# EE209_Schematic.net
KiCad netlist of a schematic drawn in Altium Designer
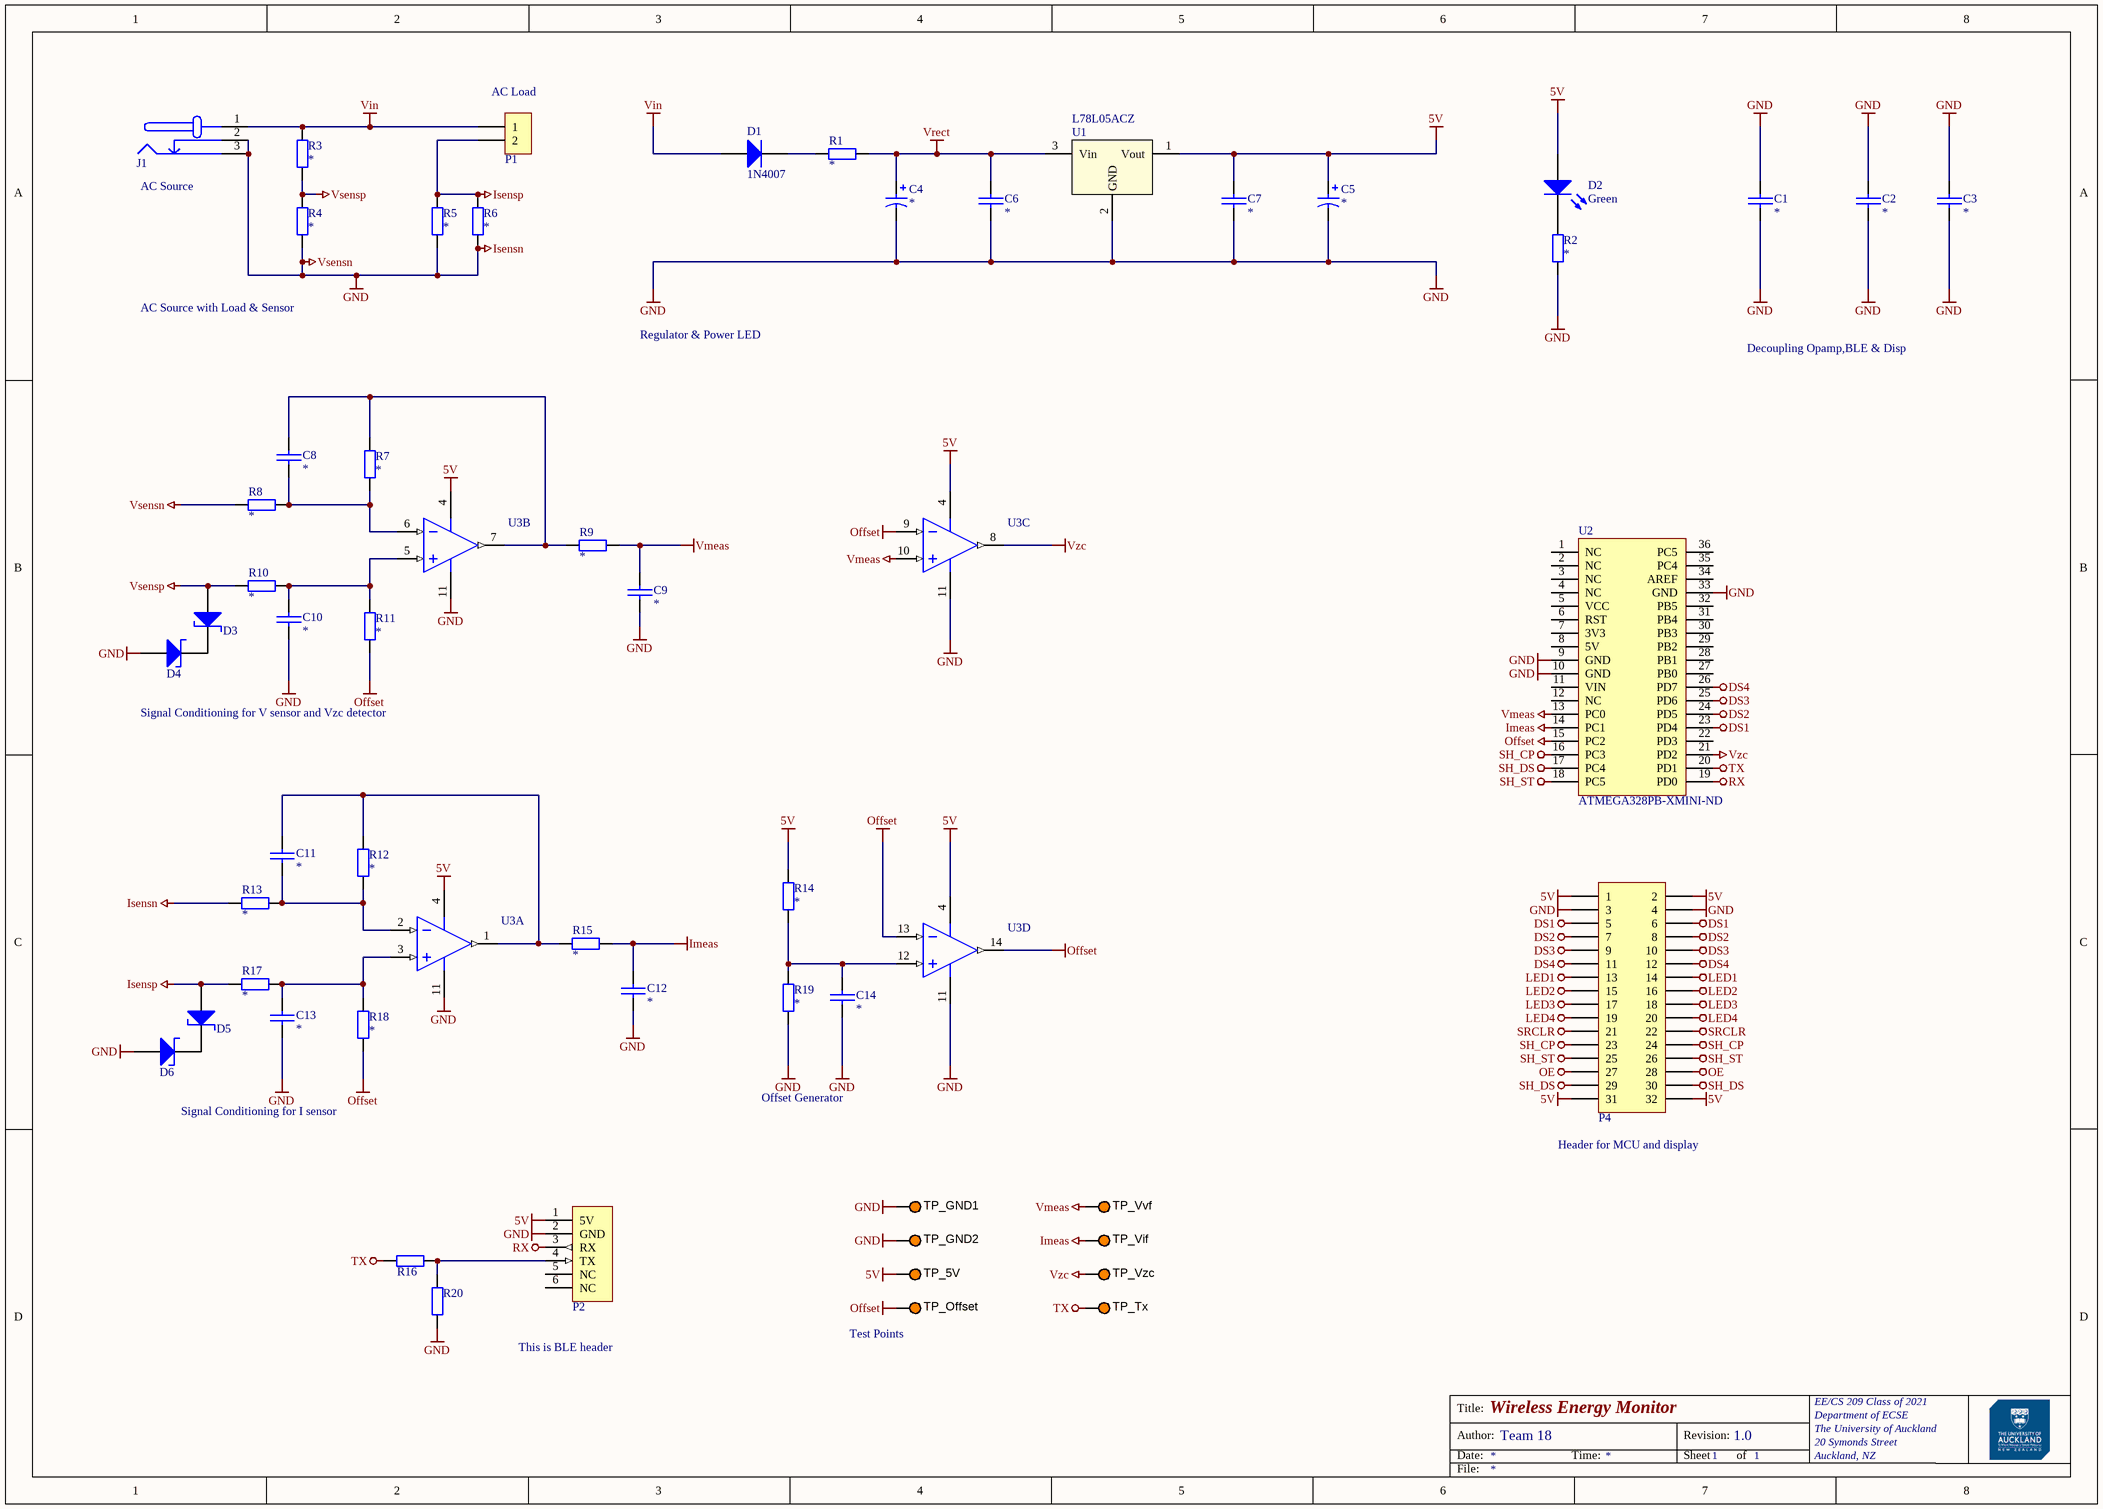
[diagram p0: EE209_Schematic.SchDoc]

(export (version "E")
  (design (tool "Eeschema 10.0.6"))
  (components
    (comp (ref "C1")
      (value "*")
      (footprint "CCAP-5P0")
      (description "TH ceramic capacitor with 5mm pitch")
      (libsource (lib "EE209_Library") (part "CerCap_TH_5P0"))
    )
    (comp (ref "C2")
      (value "*")
      (footprint "CCAP-5P0")
      (description "TH ceramic capacitor with 5mm pitch")
      (libsource (lib "EE209_Library") (part "CerCap_TH_5P0"))
    )
    (comp (ref "C3")
      (value "*")
      (footprint "CCAP-5P0")
      (description "TH ceramic capacitor with 5mm pitch")
      (libsource (lib "EE209_Library") (part "CerCap_TH_5P0"))
    )
    (comp (ref "C4")
      (value "*")
      (footprint "CAP-RAD-2.5mm Pitch")
      (description "Electrolytic capacitor with radial package, 2mm pitch and 5.2mm diameter")
      (fields (field (name "PUBLISHER") "Altium Limited"))
      (libsource (lib "EE209_Library") (part "ElecCap_TH_2P0"))
    )
    (comp (ref "C5")
      (value "*")
      (footprint "CAP-RAD-2.5mm Pitch")
      (description "Electrolytic capacitor with radial package, 2mm pitch and 5.2mm diameter")
      (fields (field (name "PUBLISHER") "Altium Limited"))
      (libsource (lib "EE209_Library") (part "ElecCap_TH_2P0"))
    )
    (comp (ref "C6")
      (value "*")
      (footprint "CCAP-5P0")
      (description "TH ceramic capacitor with 5mm pitch")
      (libsource (lib "EE209_Library") (part "CerCap_TH_5P0"))
    )
    (comp (ref "C7")
      (value "*")
      (footprint "CCAP-5P0")
      (description "TH ceramic capacitor with 5mm pitch")
      (libsource (lib "EE209_Library") (part "CerCap_TH_5P0"))
    )
    (comp (ref "C8")
      (value "*")
      (footprint "CCAP-5P0")
      (description "TH ceramic capacitor with 5mm pitch")
      (libsource (lib "EE209_Library") (part "CerCap_TH_5P0"))
    )
    (comp (ref "C9")
      (value "*")
      (footprint "CCAP-5P0")
      (description "TH ceramic capacitor with 5mm pitch")
      (libsource (lib "EE209_Library") (part "CerCap_TH_5P0"))
    )
    (comp (ref "C10")
      (value "*")
      (footprint "CCAP-5P0")
      (description "TH ceramic capacitor with 5mm pitch")
      (libsource (lib "EE209_Library") (part "CerCap_TH_5P0"))
    )
    (comp (ref "C11")
      (value "*")
      (footprint "CCAP-5P0")
      (description "TH ceramic capacitor with 5mm pitch")
      (libsource (lib "EE209_Library") (part "CerCap_TH_5P0"))
    )
    (comp (ref "C12")
      (value "*")
      (footprint "CCAP-5P0")
      (description "TH ceramic capacitor with 5mm pitch")
      (libsource (lib "EE209_Library") (part "CerCap_TH_5P0"))
    )
    (comp (ref "C13")
      (value "*")
      (footprint "CCAP-5P0")
      (description "TH ceramic capacitor with 5mm pitch")
      (libsource (lib "EE209_Library") (part "CerCap_TH_5P0"))
    )
    (comp (ref "C14")
      (value "*")
      (footprint "CCAP-5P0")
      (description "TH ceramic capacitor with 5mm pitch")
      (libsource (lib "EE209_Library") (part "CerCap_TH_5P0"))
    )
    (comp (ref "D1")
      (value "1N4007")
      (footprint "1N4007-MFG")
      (description "1N4007 1000V standard axial diode")
      (libsource (lib "EE209_Library") (part "1N4007_TH_4AX0"))
    )
    (comp (ref "D2")
      (value "Green")
      (footprint "LED")
      (description "Typical throughole GaAs LED with 2.54mm pitch")
      (fields (field (name "MANUFACTURER") "Generic Components") (field (name "PUBLISHER") "Altium Limited"))
      (libsource (lib "EE209_Library") (part "LED_TH_2P54"))
    )
    (comp (ref "D3")
      (value "BZX79-CXVX")
      (footprint "AXIAL-Zener-0.4")
      (description "Axial zener diode BZX79 series")
      (fields
        (field (name "MANUFACTURER") "Nexperia USA Inc.")
        (field (name "MANUFACTURER PART NUMBER") "BZX79-C4V7,143")
      )
      (libsource (lib "EE209_Library") (part "Zener_TH_4AX0"))
    )
    (comp (ref "D4")
      (value "BZX79-CXVX")
      (footprint "AXIAL-Zener-0.4")
      (description "Axial zener diode BZX79 series")
      (fields
        (field (name "MANUFACTURER") "Nexperia USA Inc.")
        (field (name "MANUFACTURER PART NUMBER") "BZX79-C4V7,143")
      )
      (libsource (lib "EE209_Library") (part "Zener_TH_4AX0"))
    )
    (comp (ref "D5")
      (value "BZX79-CXVX")
      (footprint "AXIAL-Zener-0.4")
      (description "Axial zener diode BZX79 series")
      (fields
        (field (name "MANUFACTURER") "Nexperia USA Inc.")
        (field (name "MANUFACTURER PART NUMBER") "BZX79-C4V7,143")
      )
      (libsource (lib "EE209_Library") (part "Zener_TH_4AX0"))
    )
    (comp (ref "D6")
      (value "BZX79-CXVX")
      (footprint "AXIAL-Zener-0.4")
      (description "Axial zener diode BZX79 series")
      (fields
        (field (name "MANUFACTURER") "Nexperia USA Inc.")
        (field (name "MANUFACTURER PART NUMBER") "BZX79-C4V7,143")
      )
      (libsource (lib "EE209_Library") (part "Zener_TH_4AX0"))
    )
    (comp (ref "J1")
      (value "DC barrel jack")
      (footprint "AC-Socket")
      (description "DC barrel jack connection to AC source")
      (libsource (lib "EE209_Library") (part "AC_Input"))
    )
    (comp (ref "P1")
      (value "Dual Banana Plugs")
      (footprint "Dual Banana Plug")
      (description "Dual banana plugs connection to the AC load")
      (fields (field (name "PUBLISHER") "Altium Limited"))
      (libsource (lib "EE209_Library") (part "AC_Output"))
    )
    (comp (ref "P2")
      (value "BLE Module Header")
      (footprint "HM10_HDR1X6")
      (description "2.54mm pitch 6-pin header for BLE module")
      (fields (field (name "PUBLISHER") "Altium Limited"))
      (libsource (lib "EE209_Library") (part "BLEModule_TH"))
    )
    (comp (ref "P4")
      (value "Display")
      (footprint "Display")
      (description "16-Pin Header Connecting Display")
      (libsource (lib "EE209_Library") (part "Display"))
    )
    (comp (ref "R1")
      (value "*")
      (footprint "AXIAL-0.4")
      (description "Through hole resistor")
      (fields (field (name "PUBLISHER") "Altium Limited"))
      (libsource (lib "EE209_Library") (part "Res_TH_0AX4"))
    )
    (comp (ref "R2")
      (value "*")
      (footprint "AXIAL-0.4")
      (description "Through hole resistor")
      (fields (field (name "PUBLISHER") "Altium Limited"))
      (libsource (lib "") (part "Res_TH_0AX4_1"))
    )
    (comp (ref "R3")
      (value "*")
      (footprint "AXIAL-0.4")
      (description "Through hole resistor")
      (fields (field (name "PUBLISHER") "Altium Limited"))
      (libsource (lib "") (part "Res_TH_0AX4_1"))
    )
    (comp (ref "R4")
      (value "*")
      (footprint "AXIAL-0.4")
      (description "Through hole resistor")
      (fields (field (name "PUBLISHER") "Altium Limited"))
      (libsource (lib "") (part "Res_TH_0AX4_1"))
    )
    (comp (ref "R5")
      (value "*")
      (footprint "AXIAL-0.4")
      (description "Through hole resistor")
      (fields (field (name "PUBLISHER") "Altium Limited"))
      (libsource (lib "") (part "Res_TH_0AX4_1"))
    )
    (comp (ref "R6")
      (value "*")
      (footprint "AXIAL-0.4")
      (description "Through hole resistor")
      (fields (field (name "PUBLISHER") "Altium Limited"))
      (libsource (lib "") (part "Res_TH_0AX4_1"))
    )
    (comp (ref "R7")
      (value "*")
      (footprint "AXIAL-0.4")
      (description "Through hole resistor")
      (fields (field (name "PUBLISHER") "Altium Limited"))
      (libsource (lib "") (part "Res_TH_0AX4_1"))
    )
    (comp (ref "R8")
      (value "*")
      (footprint "AXIAL-0.4")
      (description "Through hole resistor")
      (fields (field (name "PUBLISHER") "Altium Limited"))
      (libsource (lib "EE209_Library") (part "Res_TH_0AX4"))
    )
    (comp (ref "R9")
      (value "*")
      (footprint "AXIAL-0.4")
      (description "Through hole resistor")
      (fields (field (name "PUBLISHER") "Altium Limited"))
      (libsource (lib "EE209_Library") (part "Res_TH_0AX4"))
    )
    (comp (ref "R10")
      (value "*")
      (footprint "AXIAL-0.4")
      (description "Through hole resistor")
      (fields (field (name "PUBLISHER") "Altium Limited"))
      (libsource (lib "EE209_Library") (part "Res_TH_0AX4"))
    )
    (comp (ref "R11")
      (value "*")
      (footprint "AXIAL-0.4")
      (description "Through hole resistor")
      (fields (field (name "PUBLISHER") "Altium Limited"))
      (libsource (lib "") (part "Res_TH_0AX4_1"))
    )
    (comp (ref "R12")
      (value "*")
      (footprint "AXIAL-0.4")
      (description "Through hole resistor")
      (fields (field (name "PUBLISHER") "Altium Limited"))
      (libsource (lib "") (part "Res_TH_0AX4_1"))
    )
    (comp (ref "R13")
      (value "*")
      (footprint "AXIAL-0.4")
      (description "Through hole resistor")
      (fields (field (name "PUBLISHER") "Altium Limited"))
      (libsource (lib "EE209_Library") (part "Res_TH_0AX4"))
    )
    (comp (ref "R14")
      (value "*")
      (footprint "AXIAL-0.4")
      (description "Through hole resistor")
      (fields (field (name "PUBLISHER") "Altium Limited"))
      (libsource (lib "") (part "Res_TH_0AX4_1"))
    )
    (comp (ref "R15")
      (value "*")
      (footprint "AXIAL-0.4")
      (description "Through hole resistor")
      (fields (field (name "PUBLISHER") "Altium Limited"))
      (libsource (lib "EE209_Library") (part "Res_TH_0AX4"))
    )
    (comp (ref "R16")
      (value "*")
      (footprint "AXIAL-0.4")
      (description "Through hole resistor")
      (fields (field (name "PUBLISHER") "Altium Limited"))
      (libsource (lib "") (part "Res_TH_0AX4_2"))
    )
    (comp (ref "R17")
      (value "*")
      (footprint "AXIAL-0.4")
      (description "Through hole resistor")
      (fields (field (name "PUBLISHER") "Altium Limited"))
      (libsource (lib "EE209_Library") (part "Res_TH_0AX4"))
    )
    (comp (ref "R18")
      (value "*")
      (footprint "AXIAL-0.4")
      (description "Through hole resistor")
      (fields (field (name "PUBLISHER") "Altium Limited"))
      (libsource (lib "") (part "Res_TH_0AX4_1"))
    )
    (comp (ref "R19")
      (value "*")
      (footprint "AXIAL-0.4")
      (description "Through hole resistor")
      (fields (field (name "PUBLISHER") "Altium Limited"))
      (libsource (lib "") (part "Res_TH_0AX4_1"))
    )
    (comp (ref "R20")
      (value "*")
      (footprint "AXIAL-0.4")
      (description "Through hole resistor")
      (fields (field (name "PUBLISHER") "Altium Limited"))
      (libsource (lib "") (part "Res_TH_0AX4_1"))
    )
    (comp (ref "TP_5V")
      (value "5003")
      (footprint "TP_TH")
      (description "Test Point, Orange, 1-Pin THD, RoHS")
      (libsource (lib "EE209_Library") (part "TestPoint"))
    )
    (comp (ref "TP_GND1")
      (value "5003")
      (footprint "TP_TH")
      (description "Test Point, Orange, 1-Pin THD, RoHS")
      (libsource (lib "EE209_Library") (part "TestPoint"))
    )
    (comp (ref "TP_GND2")
      (value "5003")
      (footprint "TP_TH")
      (description "Test Point, Orange, 1-Pin THD, RoHS")
      (libsource (lib "EE209_Library") (part "TestPoint"))
    )
    (comp (ref "TP_Offset")
      (value "5003")
      (footprint "TP_TH")
      (description "Test Point, Orange, 1-Pin THD, RoHS")
      (libsource (lib "EE209_Library") (part "TestPoint"))
    )
    (comp (ref "TP_Tx")
      (value "5003")
      (footprint "TP_TH")
      (description "Test Point, Orange, 1-Pin THD, RoHS")
      (libsource (lib "EE209_Library") (part "TestPoint"))
    )
    (comp (ref "TP_Vif")
      (value "5003")
      (footprint "TP_TH")
      (description "Test Point, Orange, 1-Pin THD, RoHS")
      (libsource (lib "EE209_Library") (part "TestPoint"))
    )
    (comp (ref "TP_Vvf")
      (value "5003")
      (footprint "TP_TH")
      (description "Test Point, Orange, 1-Pin THD, RoHS")
      (libsource (lib "EE209_Library") (part "TestPoint"))
    )
    (comp (ref "TP_Vzc")
      (value "5003")
      (footprint "TP_TH")
      (description "Test Point, Orange, 1-Pin THD, RoHS")
      (libsource (lib "EE209_Library") (part "TestPoint"))
    )
    (comp (ref "U1")
      (value "L78L05ACZ")
      (footprint "TO-92")
      (description "Voltage Regulator 5V")
      (fields
        (field (name "MANUFACTURER") "ON Semiconductor")
        (field (name "MANUFACTURER PART NUMBER") "LM78L05ACZX")
      )
      (libsource (lib "EE209_Library") (part "L78L05_TH_TO92"))
    )
    (comp (ref "U2")
      (value "ATmega328PB Xplained Mini Header")
      (footprint "ATmeg328P Xplained")
      (description "Dual 18-pin headers connecting to ATmega328PB Xplained Mini")
      (fields
        (field (name "MANUFACTURER") "Microchip Technology")
        (field (name "MANUFACTURER PART NUMBER") "ATMEGA328PB-XMINI")
        (field (name "SUPPLIER PART NUMBER 1") "ATMEGA328PB-XMINI-ND")
      )
      (libsource (lib "EE209_Library") (part "ATmega328PBXplained_TH"))
    )
    (comp (ref "U3")
      (value "LM324")
      (footprint "DIP-14")
      (description "IC OPAMP GP 14DIP")
      (fields
        (field (name "MANUFACTURER") "ON Semiconductor")
        (field (name "MANUFACTURER PART NUMBER") "LM324N")
      )
      (libsource (lib "EE209_Library") (part "LM324N_TH_DIP16"))
    )
  )
  (nets
    (net (code "1") (name "5V") (class "Default")
      (node (ref "C5") (pin "1") (pinfunction "1_1") (pintype "passive"))
      (node (ref "C7") (pin "1") (pinfunction "1_1") (pintype "passive"))
      (node (ref "D2") (pin "1") (pinfunction "A_1") (pintype "passive"))
      (node (ref "P2") (pin "1") (pinfunction "5V_1") (pintype "passive"))
      (node (ref "P4") (pin "1") (pinfunction "1_1") (pintype "passive"))
      (node (ref "P4") (pin "2") (pinfunction "2_2") (pintype "passive"))
      (node (ref "P4") (pin "31") (pinfunction "31_31") (pintype "passive"))
      (node (ref "P4") (pin "32") (pinfunction "32_32") (pintype "passive"))
      (node (ref "R14") (pin "2") (pinfunction "2_2") (pintype "passive"))
      (node (ref "TP_5V") (pin "1") (pinfunction "1_1") (pintype "passive"))
      (node (ref "U1") (pin "1") (pinfunction "Vout_1") (pintype "passive"))
      (node (ref "U3") (pin "4") (pinfunction "VDD_4") (pintype "power_in"))
    )
    (net (code "2") (name "DS1") (class "Default")
      (node (ref "P4") (pin "5") (pinfunction "5_5") (pintype "passive"))
      (node (ref "P4") (pin "6") (pinfunction "6_6") (pintype "passive"))
      (node (ref "U2") (pin "23") (pinfunction "PD4_23") (pintype "passive"))
    )
    (net (code "3") (name "DS2") (class "Default")
      (node (ref "P4") (pin "7") (pinfunction "7_7") (pintype "passive"))
      (node (ref "P4") (pin "8") (pinfunction "8_8") (pintype "passive"))
      (node (ref "U2") (pin "24") (pinfunction "PD5_24") (pintype "passive"))
    )
    (net (code "4") (name "DS3") (class "Default")
      (node (ref "P4") (pin "10") (pinfunction "10_10") (pintype "passive"))
      (node (ref "P4") (pin "9") (pinfunction "9_9") (pintype "passive"))
      (node (ref "U2") (pin "25") (pinfunction "PD6_25") (pintype "passive"))
    )
    (net (code "5") (name "DS4") (class "Default")
      (node (ref "P4") (pin "11") (pinfunction "11_11") (pintype "passive"))
      (node (ref "P4") (pin "12") (pinfunction "12_12") (pintype "passive"))
      (node (ref "U2") (pin "26") (pinfunction "PD7_26") (pintype "passive"))
    )
    (net (code "6") (name "GND") (class "Default")
      (node (ref "C1") (pin "1") (pinfunction "1_1") (pintype "passive"))
      (node (ref "C1") (pin "2") (pinfunction "2_2") (pintype "passive"))
      (node (ref "C10") (pin "2") (pinfunction "2_2") (pintype "passive"))
      (node (ref "C12") (pin "2") (pinfunction "2_2") (pintype "passive"))
      (node (ref "C13") (pin "2") (pinfunction "2_2") (pintype "passive"))
      (node (ref "C14") (pin "2") (pinfunction "2_2") (pintype "passive"))
      (node (ref "C2") (pin "1") (pinfunction "1_1") (pintype "passive"))
      (node (ref "C2") (pin "2") (pinfunction "2_2") (pintype "passive"))
      (node (ref "C3") (pin "1") (pinfunction "1_1") (pintype "passive"))
      (node (ref "C3") (pin "2") (pinfunction "2_2") (pintype "passive"))
      (node (ref "C4") (pin "2") (pinfunction "2_2") (pintype "passive"))
      (node (ref "C5") (pin "2") (pinfunction "2_2") (pintype "passive"))
      (node (ref "C6") (pin "2") (pinfunction "2_2") (pintype "passive"))
      (node (ref "C7") (pin "2") (pinfunction "2_2") (pintype "passive"))
      (node (ref "C9") (pin "2") (pinfunction "2_2") (pintype "passive"))
      (node (ref "D4") (pin "1") (pinfunction "A_1") (pintype "passive"))
      (node (ref "D6") (pin "1") (pinfunction "A_1") (pintype "passive"))
      (node (ref "J1") (pin "2") (pinfunction "GND_ALT_2") (pintype "power_in"))
      (node (ref "J1") (pin "3") (pinfunction "GND_3") (pintype "power_in"))
      (node (ref "P2") (pin "2") (pinfunction "GND_2") (pintype "passive"))
      (node (ref "P4") (pin "3") (pinfunction "3_3") (pintype "passive"))
      (node (ref "P4") (pin "4") (pinfunction "4_4") (pintype "passive"))
      (node (ref "R13") (pin "1") (pinfunction "1_1") (pintype "passive"))
      (node (ref "R19") (pin "1") (pinfunction "1_1") (pintype "passive"))
      (node (ref "R2") (pin "1") (pinfunction "1_1") (pintype "passive"))
      (node (ref "R20") (pin "1") (pinfunction "1_1") (pintype "passive"))
      (node (ref "R4") (pin "1") (pinfunction "1_1") (pintype "passive"))
      (node (ref "R5") (pin "1") (pinfunction "1_1") (pintype "passive"))
      (node (ref "R6") (pin "1") (pinfunction "1_1") (pintype "passive"))
      (node (ref "R8") (pin "1") (pinfunction "1_1") (pintype "passive"))
      (node (ref "TP_GND1") (pin "1") (pinfunction "1_1") (pintype "passive"))
      (node (ref "TP_GND2") (pin "1") (pinfunction "1_1") (pintype "passive"))
      (node (ref "U1") (pin "2") (pinfunction "GND_2") (pintype "passive"))
      (node (ref "U2") (pin "10") (pinfunction "GND_10") (pintype "power_in"))
      (node (ref "U2") (pin "33") (pinfunction "GND_33") (pintype "passive"))
      (node (ref "U2") (pin "9") (pinfunction "GND_9") (pintype "power_in"))
      (node (ref "U3") (pin "11") (pinfunction "VSS_11") (pintype "power_in"))
    )
    (net (code "7") (name "Imeas") (class "Default")
      (node (ref "C12") (pin "1") (pinfunction "1_1") (pintype "passive"))
      (node (ref "R15") (pin "2") (pinfunction "2_2") (pintype "passive"))
      (node (ref "TP_Vif") (pin "1") (pinfunction "1_1") (pintype "passive"))
      (node (ref "U2") (pin "14") (pinfunction "PC1_14") (pintype "passive"))
    )
    (net (code "8") (name "Isensp") (class "Default")
      (node (ref "D5") (pin "1") (pinfunction "A_1") (pintype "passive"))
      (node (ref "P1") (pin "2") (pinfunction "2_2") (pintype "passive"))
      (node (ref "R17") (pin "1") (pinfunction "1_1") (pintype "passive"))
      (node (ref "R5") (pin "2") (pinfunction "2_2") (pintype "passive"))
      (node (ref "R6") (pin "2") (pinfunction "2_2") (pintype "passive"))
    )
    (net (code "9") (name "LED1") (class "Default")
      (node (ref "P4") (pin "13") (pinfunction "13_13") (pintype "passive"))
      (node (ref "P4") (pin "14") (pinfunction "14_14") (pintype "passive"))
    )
    (net (code "10") (name "LED2") (class "Default")
      (node (ref "P4") (pin "15") (pinfunction "15_15") (pintype "passive"))
      (node (ref "P4") (pin "16") (pinfunction "16_16") (pintype "passive"))
    )
    (net (code "11") (name "LED3") (class "Default")
      (node (ref "P4") (pin "17") (pinfunction "17_17") (pintype "passive"))
      (node (ref "P4") (pin "18") (pinfunction "18_18") (pintype "passive"))
    )
    (net (code "12") (name "LED4") (class "Default")
      (node (ref "P4") (pin "19") (pinfunction "19_19") (pintype "passive"))
      (node (ref "P4") (pin "20") (pinfunction "20_20") (pintype "passive"))
    )
    (net (code "13") (name "Net-(D1-K)") (class "Default")
      (node (ref "D1") (pin "2") (pinfunction "K_2") (pintype "passive"))
      (node (ref "R1") (pin "1") (pinfunction "1_1") (pintype "passive"))
    )
    (net (code "14") (name "Net-(D2-K)") (class "Default")
      (node (ref "D2") (pin "2") (pinfunction "K_2") (pintype "passive"))
      (node (ref "R2") (pin "2") (pinfunction "2_2") (pintype "passive"))
    )
    (net (code "15") (name "Net-(D3-K)") (class "Default")
      (node (ref "D3") (pin "2") (pinfunction "K_2") (pintype "passive"))
      (node (ref "D4") (pin "2") (pinfunction "K_2") (pintype "passive"))
    )
    (net (code "16") (name "Net-(D5-K)") (class "Default")
      (node (ref "D5") (pin "2") (pinfunction "K_2") (pintype "passive"))
      (node (ref "D6") (pin "2") (pinfunction "K_2") (pintype "passive"))
    )
    (net (code "17") (name "Net-(P2-TX)") (class "Default")
      (node (ref "P2") (pin "4") (pinfunction "TX_4") (pintype "input"))
      (node (ref "R16") (pin "1") (pinfunction "1_1") (pintype "passive"))
      (node (ref "R20") (pin "2") (pinfunction "2_2") (pintype "passive"))
    )
    (net (code "18") (name "Net-(U3A-VINA+)") (class "Default")
      (node (ref "C13") (pin "1") (pinfunction "1_1") (pintype "passive"))
      (node (ref "R17") (pin "2") (pinfunction "2_2") (pintype "passive"))
      (node (ref "R18") (pin "2") (pinfunction "2_2") (pintype "passive"))
      (node (ref "U3") (pin "3") (pinfunction "VINA+_3") (pintype "input"))
    )
    (net (code "19") (name "Net-(U3A-VINA-)") (class "Default")
      (node (ref "C11") (pin "2") (pinfunction "2_2") (pintype "passive"))
      (node (ref "R12") (pin "1") (pinfunction "1_1") (pintype "passive"))
      (node (ref "R13") (pin "2") (pinfunction "2_2") (pintype "passive"))
      (node (ref "U3") (pin "2") (pinfunction "VINA-_2") (pintype "input"))
    )
    (net (code "20") (name "Net-(U3A-VOUTA)") (class "Default")
      (node (ref "C11") (pin "1") (pinfunction "1_1") (pintype "passive"))
      (node (ref "R12") (pin "2") (pinfunction "2_2") (pintype "passive"))
      (node (ref "R15") (pin "1") (pinfunction "1_1") (pintype "passive"))
      (node (ref "U3") (pin "1") (pinfunction "VOUTA_1") (pintype "output"))
    )
    (net (code "21") (name "Net-(U3B-VINB+)") (class "Default")
      (node (ref "C10") (pin "1") (pinfunction "1_1") (pintype "passive"))
      (node (ref "R10") (pin "2") (pinfunction "2_2") (pintype "passive"))
      (node (ref "R11") (pin "2") (pinfunction "2_2") (pintype "passive"))
      (node (ref "U3") (pin "5") (pinfunction "VINB+_5") (pintype "input"))
    )
    (net (code "22") (name "Net-(U3B-VINB-)") (class "Default")
      (node (ref "C8") (pin "2") (pinfunction "2_2") (pintype "passive"))
      (node (ref "R7") (pin "1") (pinfunction "1_1") (pintype "passive"))
      (node (ref "R8") (pin "2") (pinfunction "2_2") (pintype "passive"))
      (node (ref "U3") (pin "6") (pinfunction "VINB-_6") (pintype "input"))
    )
    (net (code "23") (name "Net-(U3B-VOUTB)") (class "Default")
      (node (ref "C8") (pin "1") (pinfunction "1_1") (pintype "passive"))
      (node (ref "R7") (pin "2") (pinfunction "2_2") (pintype "passive"))
      (node (ref "R9") (pin "1") (pinfunction "1_1") (pintype "passive"))
      (node (ref "U3") (pin "7") (pinfunction "VOUTB_7") (pintype "output"))
    )
    (net (code "24") (name "Net-(U3D-VIND+)") (class "Default")
      (node (ref "C14") (pin "1") (pinfunction "1_1") (pintype "passive"))
      (node (ref "R14") (pin "1") (pinfunction "1_1") (pintype "passive"))
      (node (ref "R19") (pin "2") (pinfunction "2_2") (pintype "passive"))
      (node (ref "U3") (pin "12") (pinfunction "VIND+_12") (pintype "input"))
    )
    (net (code "25") (name "OE") (class "Default")
      (node (ref "P4") (pin "27") (pinfunction "27_27") (pintype "passive"))
      (node (ref "P4") (pin "28") (pinfunction "28_28") (pintype "passive"))
    )
    (net (code "26") (name "Offset") (class "Default")
      (node (ref "R11") (pin "1") (pinfunction "1_1") (pintype "passive"))
      (node (ref "R18") (pin "1") (pinfunction "1_1") (pintype "passive"))
      (node (ref "TP_Offset") (pin "1") (pinfunction "1_1") (pintype "passive"))
      (node (ref "U2") (pin "15") (pinfunction "PC2_15") (pintype "passive"))
      (node (ref "U3") (pin "13") (pinfunction "VIND-_13") (pintype "input"))
      (node (ref "U3") (pin "14") (pinfunction "VOUTD_14") (pintype "output"))
      (node (ref "U3") (pin "9") (pinfunction "VINC-_9") (pintype "input"))
    )
    (net (code "27") (name "RX") (class "Default")
      (node (ref "P2") (pin "3") (pinfunction "RX_3") (pintype "output"))
      (node (ref "U2") (pin "19") (pinfunction "PD0_19") (pintype "passive"))
    )
    (net (code "28") (name "SH_CP") (class "Default")
      (node (ref "P4") (pin "23") (pinfunction "23_23") (pintype "passive"))
      (node (ref "P4") (pin "24") (pinfunction "24_24") (pintype "passive"))
      (node (ref "U2") (pin "16") (pinfunction "PC3_16") (pintype "passive"))
    )
    (net (code "29") (name "SH_DS") (class "Default")
      (node (ref "P4") (pin "29") (pinfunction "29_29") (pintype "passive"))
      (node (ref "P4") (pin "30") (pinfunction "30_30") (pintype "passive"))
      (node (ref "U2") (pin "17") (pinfunction "PC4_17") (pintype "passive"))
    )
    (net (code "30") (name "SH_ST") (class "Default")
      (node (ref "P4") (pin "25") (pinfunction "25_25") (pintype "passive"))
      (node (ref "P4") (pin "26") (pinfunction "26_26") (pintype "passive"))
      (node (ref "U2") (pin "18") (pinfunction "PC5_18") (pintype "passive"))
    )
    (net (code "31") (name "SRCLR") (class "Default")
      (node (ref "P4") (pin "21") (pinfunction "21_21") (pintype "passive"))
      (node (ref "P4") (pin "22") (pinfunction "22_22") (pintype "passive"))
    )
    (net (code "32") (name "TX") (class "Default")
      (node (ref "R16") (pin "2") (pinfunction "2_2") (pintype "passive"))
      (node (ref "TP_Tx") (pin "1") (pinfunction "1_1") (pintype "passive"))
      (node (ref "U2") (pin "20") (pinfunction "PD1_20") (pintype "passive"))
    )
    (net (code "33") (name "Vin") (class "Default")
      (node (ref "D1") (pin "1") (pinfunction "A_1") (pintype "passive"))
      (node (ref "J1") (pin "1") (pinfunction "VCC_1") (pintype "power_in"))
      (node (ref "P1") (pin "1") (pinfunction "1_1") (pintype "passive"))
      (node (ref "R3") (pin "2") (pinfunction "2_2") (pintype "passive"))
    )
    (net (code "34") (name "Vmeas") (class "Default")
      (node (ref "C9") (pin "1") (pinfunction "1_1") (pintype "passive"))
      (node (ref "R9") (pin "2") (pinfunction "2_2") (pintype "passive"))
      (node (ref "TP_Vvf") (pin "1") (pinfunction "1_1") (pintype "passive"))
      (node (ref "U2") (pin "13") (pinfunction "PC0_13") (pintype "passive"))
      (node (ref "U3") (pin "10") (pinfunction "VINC+_10") (pintype "input"))
    )
    (net (code "35") (name "Vrect") (class "Default")
      (node (ref "C4") (pin "1") (pinfunction "1_1") (pintype "passive"))
      (node (ref "C6") (pin "1") (pinfunction "1_1") (pintype "passive"))
      (node (ref "R1") (pin "2") (pinfunction "2_2") (pintype "passive"))
      (node (ref "U1") (pin "3") (pinfunction "Vin_3") (pintype "passive"))
    )
    (net (code "36") (name "Vsensp") (class "Default")
      (node (ref "D3") (pin "1") (pinfunction "A_1") (pintype "passive"))
      (node (ref "R10") (pin "1") (pinfunction "1_1") (pintype "passive"))
      (node (ref "R3") (pin "1") (pinfunction "1_1") (pintype "passive"))
      (node (ref "R4") (pin "2") (pinfunction "2_2") (pintype "passive"))
    )
    (net (code "37") (name "Vzc") (class "Default")
      (node (ref "TP_Vzc") (pin "1") (pinfunction "1_1") (pintype "passive"))
      (node (ref "U2") (pin "21") (pinfunction "PD2_21") (pintype "passive"))
      (node (ref "U3") (pin "8") (pinfunction "VOUTC_8") (pintype "output"))
    )
    (net (code "38") (name "unconnected-(P2-NC-Pad5)") (class "Default")
      (node (ref "P2") (pin "5") (pinfunction "NC_5") (pintype "passive"))
    )
    (net (code "39") (name "unconnected-(P2-NC-Pad6)") (class "Default")
      (node (ref "P2") (pin "6") (pinfunction "NC_6") (pintype "passive"))
    )
    (net (code "40") (name "unconnected-(U2-3V3-Pad7)") (class "Default")
      (node (ref "U2") (pin "7") (pinfunction "3V3_7") (pintype "passive"))
    )
    (net (code "41") (name "unconnected-(U2-5V-Pad8)") (class "Default")
      (node (ref "U2") (pin "8") (pinfunction "5V_8") (pintype "power_in"))
    )
    (net (code "42") (name "unconnected-(U2-AREF-Pad34)") (class "Default")
      (node (ref "U2") (pin "34") (pinfunction "AREF_34") (pintype "passive"))
    )
    (net (code "43") (name "unconnected-(U2-NC-Pad1)") (class "Default")
      (node (ref "U2") (pin "1") (pinfunction "NC_1") (pintype "passive"))
    )
    (net (code "44") (name "unconnected-(U2-NC-Pad2)") (class "Default")
      (node (ref "U2") (pin "2") (pinfunction "NC_2") (pintype "passive"))
    )
    (net (code "45") (name "unconnected-(U2-NC-Pad3)") (class "Default")
      (node (ref "U2") (pin "3") (pinfunction "NC_3") (pintype "passive"))
    )
    (net (code "46") (name "unconnected-(U2-NC-Pad4)") (class "Default")
      (node (ref "U2") (pin "4") (pinfunction "NC_4") (pintype "passive"))
    )
    (net (code "47") (name "unconnected-(U2-NC-Pad12)") (class "Default")
      (node (ref "U2") (pin "12") (pinfunction "NC_12") (pintype "passive"))
    )
    (net (code "48") (name "unconnected-(U2-PB0-Pad27)") (class "Default")
      (node (ref "U2") (pin "27") (pinfunction "PB0_27") (pintype "passive"))
    )
    (net (code "49") (name "unconnected-(U2-PB1-Pad28)") (class "Default")
      (node (ref "U2") (pin "28") (pinfunction "PB1_28") (pintype "passive"))
    )
    (net (code "50") (name "unconnected-(U2-PB2-Pad29)") (class "Default")
      (node (ref "U2") (pin "29") (pinfunction "PB2_29") (pintype "passive"))
    )
    (net (code "51") (name "unconnected-(U2-PB3-Pad30)") (class "Default")
      (node (ref "U2") (pin "30") (pinfunction "PB3_30") (pintype "passive"))
    )
    (net (code "52") (name "unconnected-(U2-PB4-Pad31)") (class "Default")
      (node (ref "U2") (pin "31") (pinfunction "PB4_31") (pintype "passive"))
    )
    (net (code "53") (name "unconnected-(U2-PB5-Pad32)") (class "Default")
      (node (ref "U2") (pin "32") (pinfunction "PB5_32") (pintype "passive"))
    )
    (net (code "54") (name "unconnected-(U2-PC4-Pad35)") (class "Default")
      (node (ref "U2") (pin "35") (pinfunction "PC4_35") (pintype "passive"))
    )
    (net (code "55") (name "unconnected-(U2-PC5-Pad36)") (class "Default")
      (node (ref "U2") (pin "36") (pinfunction "PC5_36") (pintype "passive"))
    )
    (net (code "56") (name "unconnected-(U2-PD3-Pad22)") (class "Default")
      (node (ref "U2") (pin "22") (pinfunction "PD3_22") (pintype "passive"))
    )
    (net (code "57") (name "unconnected-(U2-RST-Pad6)") (class "Default")
      (node (ref "U2") (pin "6") (pinfunction "RST_6") (pintype "passive"))
    )
    (net (code "58") (name "unconnected-(U2-VCC-Pad5)") (class "Default")
      (node (ref "U2") (pin "5") (pinfunction "VCC_5") (pintype "power_in"))
    )
    (net (code "59") (name "unconnected-(U2-VIN-Pad11)") (class "Default")
      (node (ref "U2") (pin "11") (pinfunction "VIN_11") (pintype "power_in"))
    )
  )
)
